# HMI.net
KiCad netlist of a schematic drawn in Altium Designer
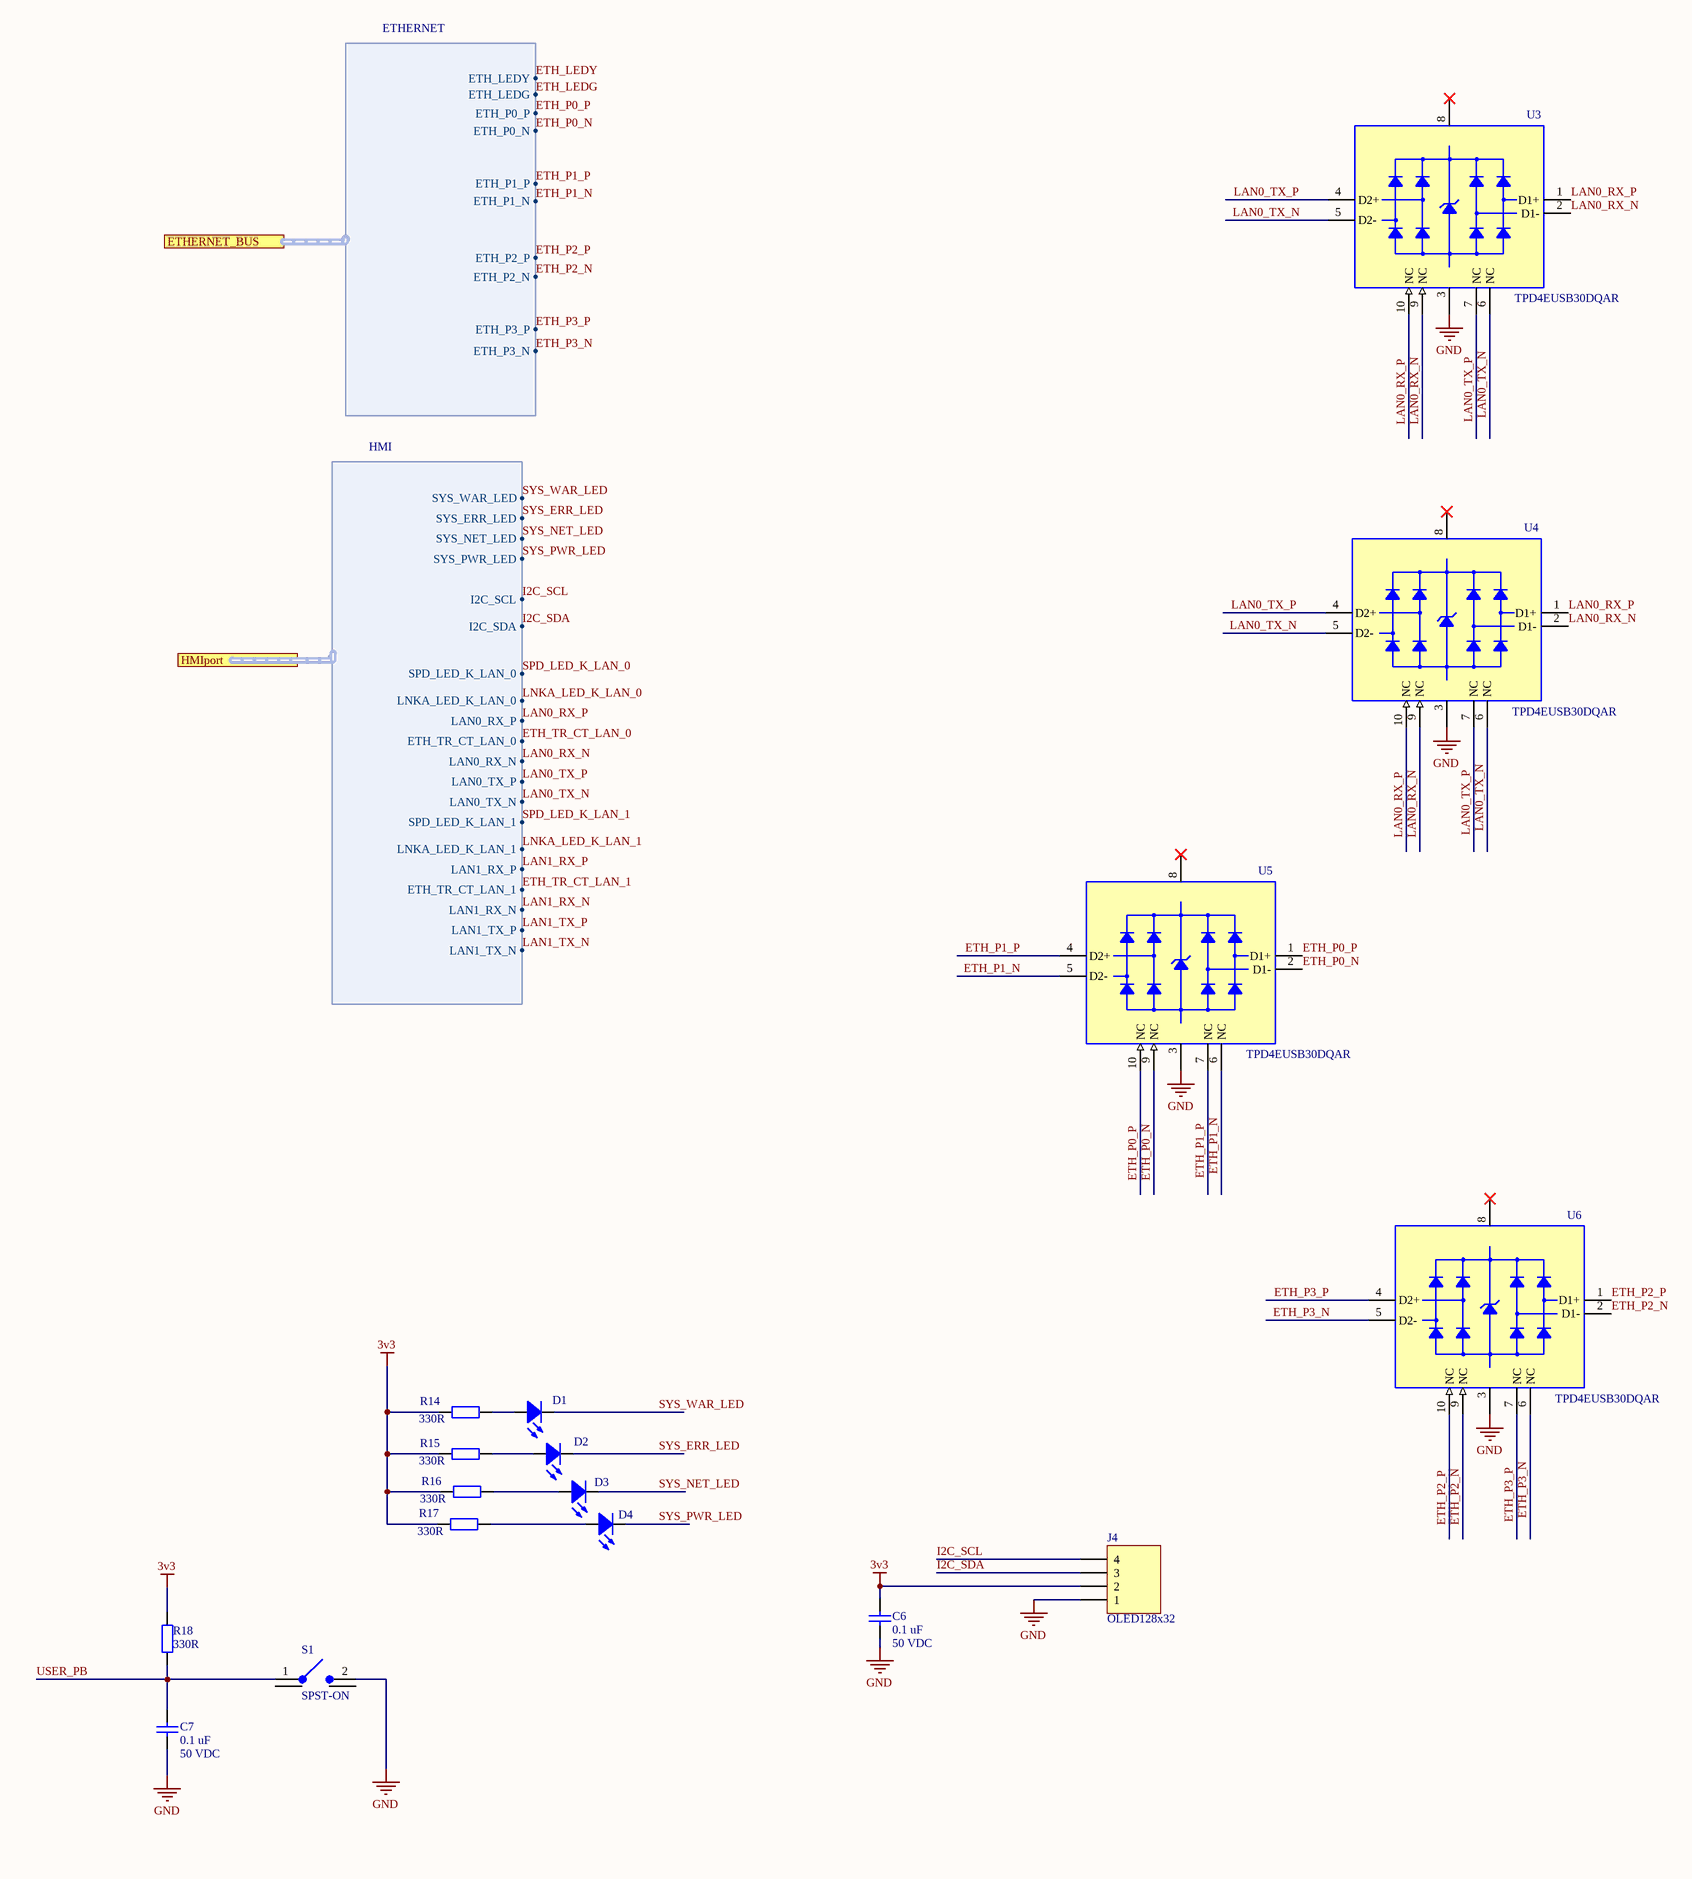
[diagram p0: HMI.SchDoc, left]
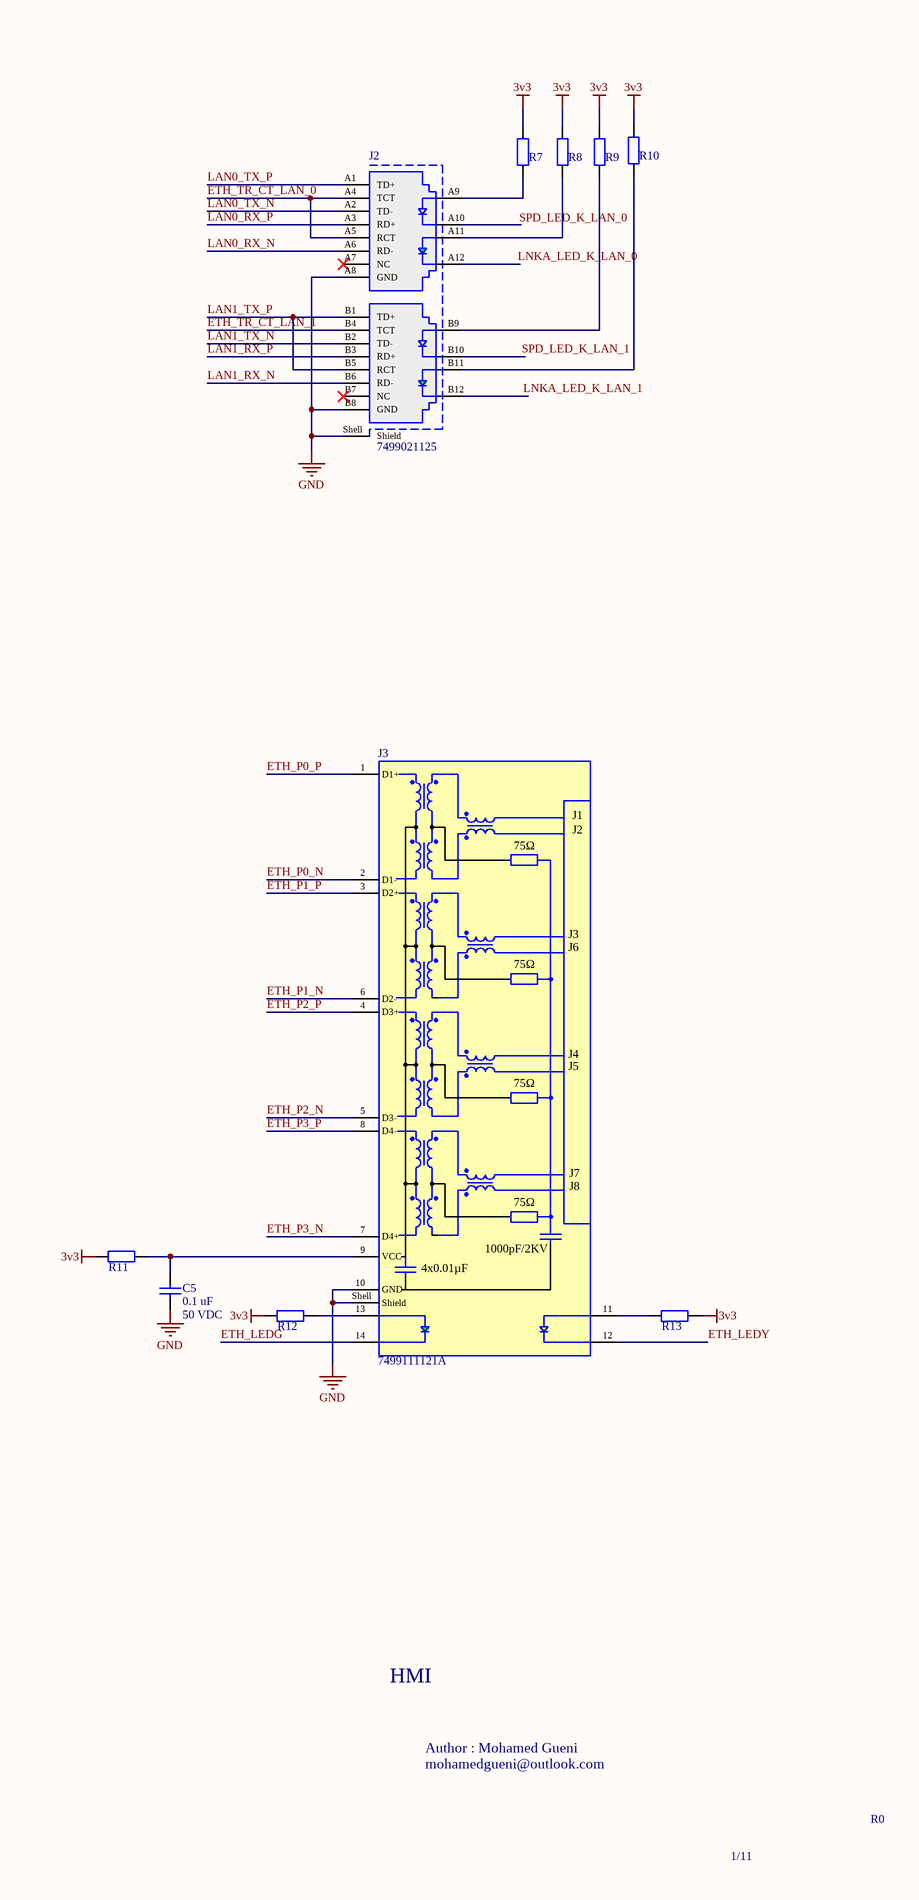
[diagram p1: HMI.SchDoc, right]

(export (version "E")
  (design (tool "Eeschema 10.0.6"))
  (components
    (comp (ref "C5")
      (value "Capacitor")
      (footprint "CAPC1608N")
      (fields
        (field (name "PART NUMBER") "CAP-000000003")
        (field (name "VALUE 1") "0.1 uF")
        (field (name "VALUE 2") "50 VDC")
      )
      (libsource (lib "DB") (part "Capacitor"))
    )
    (comp (ref "C6")
      (value "Capacitor")
      (footprint "CAPC1608N")
      (fields
        (field (name "PART NUMBER") "CAP-000000003")
        (field (name "VALUE 1") "0.1 uF")
        (field (name "VALUE 2") "50 VDC")
      )
      (libsource (lib "DB") (part "Capacitor"))
    )
    (comp (ref "C7")
      (value "Capacitor")
      (footprint "CAPC1608N")
      (fields
        (field (name "PART NUMBER") "CAP-000000003")
        (field (name "VALUE 1") "0.1 uF")
        (field (name "VALUE 2") "50 VDC")
      )
      (libsource (lib "DB") (part "Capacitor"))
    )
    (comp (ref "D1")
      (value "150060BS75000")
      (footprint "LED0603")
      (fields (field (name "PART NUMBER") "LED-000000003"))
      (libsource (lib "DB") (part "LED"))
    )
    (comp (ref "D2")
      (value "150060RS75000")
      (footprint "LED0603")
      (fields (field (name "PART NUMBER") "LED-000000001"))
      (libsource (lib "DB") (part "LED"))
    )
    (comp (ref "D3")
      (value "150060GS75000")
      (footprint "LED0603")
      (fields (field (name "PART NUMBER") "LED-000000002"))
      (libsource (lib "DB") (part "LED"))
    )
    (comp (ref "D4")
      (value "150060GS75000")
      (footprint "LED0603")
      (fields (field (name "PART NUMBER") "LED-000000002"))
      (libsource (lib "DB") (part "LED"))
    )
    (comp (ref "J2")
      (value "7499021125")
      (footprint "WE-RJ45-7499021125")
      (fields (field (name "PART NUMBER") "CON-000000008"))
      (libsource (lib "DB") (part "WE-RJ45-7499021125"))
    )
    (comp (ref "J3")
      (value "7499111121A")
      (footprint "WE-RJ45-7499111121A")
      (fields (field (name "PART NUMBER") "CON-000000002"))
      (libsource (lib "DB") (part "WE-RJ45-7499111121A"))
    )
    (comp (ref "J4")
      (value "OLED128x32")
      (footprint "OLED128x32")
      (fields (field (name "PART NUMBER") "CON-000000009"))
      (libsource (lib "DB") (part "OLED128x32"))
    )
    (comp (ref "R7")
      (value "Resistor")
      (footprint "RESC1608N")
      (fields (field (name "PART NUMBER") "RES-000000008"))
      (libsource (lib "") (part "Resistor_1"))
    )
    (comp (ref "R8")
      (value "Resistor")
      (footprint "RESC1608N")
      (fields (field (name "PART NUMBER") "RES-000000008"))
      (libsource (lib "") (part "Resistor_1"))
    )
    (comp (ref "R9")
      (value "Resistor")
      (footprint "RESC1608N")
      (fields (field (name "PART NUMBER") "RES-000000008"))
      (libsource (lib "") (part "Resistor_1"))
    )
    (comp (ref "R10")
      (value "Resistor")
      (footprint "RESC1608N")
      (fields (field (name "PART NUMBER") "RES-000000008"))
      (libsource (lib "") (part "Resistor_1"))
    )
    (comp (ref "R11")
      (value "Resistor")
      (footprint "RESC1608N")
      (fields (field (name "PART NUMBER") "RES-000000008"))
      (libsource (lib "") (part "Resistor_2"))
    )
    (comp (ref "R12")
      (value "Resistor")
      (footprint "RESC1608N")
      (fields (field (name "PART NUMBER") "RES-000000008"))
      (libsource (lib "") (part "Resistor_2"))
    )
    (comp (ref "R13")
      (value "Resistor")
      (footprint "RESC1608N")
      (fields (field (name "PART NUMBER") "RES-000000008"))
      (libsource (lib "DB") (part "Resistor"))
    )
    (comp (ref "R14")
      (value "Resistor")
      (footprint "RESC1608N")
      (fields (field (name "PART NUMBER") "RES-000000008") (field (name "VALUE 1") "330R"))
      (libsource (lib "DB") (part "Resistor"))
    )
    (comp (ref "R15")
      (value "Resistor")
      (footprint "RESC1608N")
      (fields (field (name "PART NUMBER") "RES-000000008") (field (name "VALUE 1") "330R"))
      (libsource (lib "DB") (part "Resistor"))
    )
    (comp (ref "R16")
      (value "Resistor")
      (footprint "RESC1608N")
      (fields (field (name "PART NUMBER") "RES-000000008") (field (name "VALUE 1") "330R"))
      (libsource (lib "DB") (part "Resistor"))
    )
    (comp (ref "R17")
      (value "Resistor")
      (footprint "RESC1608N")
      (fields (field (name "PART NUMBER") "RES-000000008") (field (name "VALUE 1") "330R"))
      (libsource (lib "DB") (part "Resistor"))
    )
    (comp (ref "R18")
      (value "Resistor")
      (footprint "RESC1608N")
      (fields (field (name "PART NUMBER") "RES-000000008") (field (name "VALUE 1") "330R"))
      (libsource (lib "") (part "Resistor_1"))
    )
    (comp (ref "S1")
      (value "SPST-ON")
      (footprint "118250272")
      (fields (field (name "PART NUMBER") "S-000000001"))
      (libsource (lib "DB") (part "SPST-ON"))
    )
    (comp (ref "U3")
      (value "TPD4EUSB30DQAR")
      (footprint "USON-10")
      (fields (field (name "PART NUMBER") "TVS-000000001"))
      (libsource (lib "DB") (part "TVS4"))
    )
    (comp (ref "U4")
      (value "TPD4EUSB30DQAR")
      (footprint "USON-10")
      (fields (field (name "PART NUMBER") "TVS-000000001"))
      (libsource (lib "DB") (part "TVS4"))
    )
    (comp (ref "U5")
      (value "TPD4EUSB30DQAR")
      (footprint "USON-10")
      (fields (field (name "PART NUMBER") "TVS-000000001"))
      (libsource (lib "DB") (part "TVS4"))
    )
    (comp (ref "U6")
      (value "TPD4EUSB30DQAR")
      (footprint "USON-10")
      (fields (field (name "PART NUMBER") "TVS-000000001"))
      (libsource (lib "DB") (part "TVS4"))
    )
  )
  (nets
    (net (code "3") (name "/ETH_LEDG") (class "Default")
      (node (ref "J3") (pin "14") (pinfunction "14_14") (pintype "passive"))
    )
    (net (code "4") (name "/ETH_LEDY") (class "Default")
      (node (ref "J3") (pin "12") (pinfunction "12_12") (pintype "passive"))
    )
    (net (code "5") (name "/ETH_P0_N") (class "Default")
      (node (ref "J3") (pin "2") (pinfunction "D1-_2") (pintype "passive"))
      (node (ref "U5") (pin "2") (pinfunction "D1-_2") (pintype "passive"))
      (node (ref "U5") (pin "9") (pinfunction "NC_9") (pintype "input"))
    )
    (net (code "6") (name "/ETH_P0_P") (class "Default")
      (node (ref "J3") (pin "1") (pinfunction "D1+_1") (pintype "passive"))
      (node (ref "U5") (pin "1") (pinfunction "D1+_1") (pintype "passive"))
      (node (ref "U5") (pin "10") (pinfunction "NC_10") (pintype "input"))
    )
    (net (code "7") (name "/ETH_P1_N") (class "Default")
      (node (ref "J3") (pin "6") (pinfunction "D2-_6") (pintype "passive"))
      (node (ref "U5") (pin "5") (pinfunction "D2-_5") (pintype "passive"))
      (node (ref "U5") (pin "6") (pinfunction "NC_6") (pintype "passive"))
    )
    (net (code "8") (name "/ETH_P1_P") (class "Default")
      (node (ref "J3") (pin "3") (pinfunction "D2+_3") (pintype "passive"))
      (node (ref "U5") (pin "4") (pinfunction "D2+_4") (pintype "passive"))
      (node (ref "U5") (pin "7") (pinfunction "NC_7") (pintype "passive"))
    )
    (net (code "9") (name "/ETH_P2_N") (class "Default")
      (node (ref "J3") (pin "5") (pinfunction "D3-_5") (pintype "passive"))
      (node (ref "U6") (pin "2") (pinfunction "D1-_2") (pintype "passive"))
      (node (ref "U6") (pin "9") (pinfunction "NC_9") (pintype "input"))
    )
    (net (code "10") (name "/ETH_P2_P") (class "Default")
      (node (ref "J3") (pin "4") (pinfunction "D3+_4") (pintype "passive"))
      (node (ref "U6") (pin "1") (pinfunction "D1+_1") (pintype "passive"))
      (node (ref "U6") (pin "10") (pinfunction "NC_10") (pintype "input"))
    )
    (net (code "11") (name "/ETH_P3_N") (class "Default")
      (node (ref "J3") (pin "7") (pinfunction "D4+_7") (pintype "passive"))
      (node (ref "U6") (pin "5") (pinfunction "D2-_5") (pintype "passive"))
      (node (ref "U6") (pin "6") (pinfunction "NC_6") (pintype "passive"))
    )
    (net (code "12") (name "/ETH_P3_P") (class "Default")
      (node (ref "J3") (pin "8") (pinfunction "D4-_8") (pintype "passive"))
      (node (ref "U6") (pin "4") (pinfunction "D2+_4") (pintype "passive"))
      (node (ref "U6") (pin "7") (pinfunction "NC_7") (pintype "passive"))
    )
    (net (code "13") (name "/ETH_TR_CT_LAN_0") (class "Default")
      (node (ref "J2") (pin "A4") (pinfunction "TCT_A4") (pintype "passive"))
      (node (ref "J2") (pin "A5") (pinfunction "RCT_A5") (pintype "passive"))
    )
    (net (code "14") (name "/ETH_TR_CT_LAN_1") (class "Default")
      (node (ref "J2") (pin "B4") (pinfunction "TCT_B4") (pintype "passive"))
    )
    (net (code "15") (name "/I2C_SCL") (class "Default")
      (node (ref "J4") (pin "4") (pinfunction "4_4") (pintype "passive"))
    )
    (net (code "16") (name "/I2C_SDA") (class "Default")
      (node (ref "J4") (pin "3") (pinfunction "3_3") (pintype "passive"))
    )
    (net (code "17") (name "/LAN0_RX_N") (class "Default")
      (node (ref "J2") (pin "A6") (pinfunction "RD-_A6") (pintype "passive"))
      (node (ref "U3") (pin "2") (pinfunction "D1-_2") (pintype "passive"))
      (node (ref "U3") (pin "9") (pinfunction "NC_9") (pintype "input"))
      (node (ref "U4") (pin "2") (pinfunction "D1-_2") (pintype "passive"))
      (node (ref "U4") (pin "9") (pinfunction "NC_9") (pintype "input"))
    )
    (net (code "18") (name "/LAN0_RX_P") (class "Default")
      (node (ref "J2") (pin "A3") (pinfunction "RD+_A3") (pintype "passive"))
      (node (ref "U3") (pin "1") (pinfunction "D1+_1") (pintype "passive"))
      (node (ref "U3") (pin "10") (pinfunction "NC_10") (pintype "input"))
      (node (ref "U4") (pin "1") (pinfunction "D1+_1") (pintype "passive"))
      (node (ref "U4") (pin "10") (pinfunction "NC_10") (pintype "input"))
    )
    (net (code "19") (name "/LAN0_TX_N") (class "Default")
      (node (ref "J2") (pin "A2") (pinfunction "TD-_A2") (pintype "passive"))
      (node (ref "U3") (pin "5") (pinfunction "D2-_5") (pintype "passive"))
      (node (ref "U3") (pin "6") (pinfunction "NC_6") (pintype "passive"))
      (node (ref "U4") (pin "5") (pinfunction "D2-_5") (pintype "passive"))
      (node (ref "U4") (pin "6") (pinfunction "NC_6") (pintype "passive"))
    )
    (net (code "20") (name "/LAN0_TX_P") (class "Default")
      (node (ref "J2") (pin "A1") (pinfunction "TD+_A1") (pintype "passive"))
      (node (ref "U3") (pin "4") (pinfunction "D2+_4") (pintype "passive"))
      (node (ref "U3") (pin "7") (pinfunction "NC_7") (pintype "passive"))
      (node (ref "U4") (pin "4") (pinfunction "D2+_4") (pintype "passive"))
      (node (ref "U4") (pin "7") (pinfunction "NC_7") (pintype "passive"))
    )
    (net (code "21") (name "/LAN1_RX_N") (class "Default")
      (node (ref "J2") (pin "B6") (pinfunction "RD-_B6") (pintype "passive"))
    )
    (net (code "22") (name "/LAN1_RX_P") (class "Default")
      (node (ref "J2") (pin "B3") (pinfunction "RD+_B3") (pintype "passive"))
    )
    (net (code "23") (name "/LAN1_TX_N") (class "Default")
      (node (ref "J2") (pin "B2") (pinfunction "TD-_B2") (pintype "passive"))
    )
    (net (code "24") (name "/LAN1_TX_P") (class "Default")
      (node (ref "J2") (pin "B1") (pinfunction "TD+_B1") (pintype "passive"))
      (node (ref "J2") (pin "B5") (pinfunction "RCT_B5") (pintype "passive"))
    )
    (net (code "25") (name "/LNKA_LED_K_LAN_0") (class "Default")
      (node (ref "J2") (pin "A12") (pinfunction "A12_A12") (pintype "passive"))
    )
    (net (code "26") (name "/LNKA_LED_K_LAN_1") (class "Default")
      (node (ref "J2") (pin "B12") (pinfunction "B12_B12") (pintype "passive"))
    )
    (net (code "28") (name "/SPD_LED_K_LAN_1") (class "Default")
      (node (ref "J2") (pin "B10") (pinfunction "B10_B10") (pintype "passive"))
    )
    (net (code "29") (name "/SYS_ERR_LED") (class "Default")
      (node (ref "D2") (pin "1") (pinfunction "K_1") (pintype "passive"))
    )
    (net (code "30") (name "/SYS_NET_LED") (class "Default")
      (node (ref "D3") (pin "1") (pinfunction "K_1") (pintype "passive"))
    )
    (net (code "31") (name "/SYS_PWR_LED") (class "Default")
      (node (ref "D4") (pin "1") (pinfunction "K_1") (pintype "passive"))
    )
    (net (code "32") (name "/SYS_WAR_LED") (class "Default")
      (node (ref "D1") (pin "1") (pinfunction "K_1") (pintype "passive"))
    )
    (net (code "33") (name "/USER_PB") (class "Default")
      (node (ref "C7") (pin "2") (pinfunction "2_2") (pintype "passive"))
      (node (ref "R18") (pin "1") (pinfunction "1_1") (pintype "passive"))
      (node (ref "S1") (pin "1") (pinfunction "COM_1") (pintype "passive"))
    )
    (net (code "36") (name "3v3") (class "Default")
      (node (ref "C6") (pin "2") (pinfunction "2_2") (pintype "passive"))
      (node (ref "J4") (pin "2") (pinfunction "2_2") (pintype "passive"))
      (node (ref "R10") (pin "2") (pinfunction "2_2") (pintype "passive"))
      (node (ref "R11") (pin "2") (pinfunction "2_2") (pintype "passive"))
      (node (ref "R12") (pin "2") (pinfunction "2_2") (pintype "passive"))
      (node (ref "R13") (pin "2") (pinfunction "2_2") (pintype "passive"))
      (node (ref "R14") (pin "1") (pinfunction "1_1") (pintype "passive"))
      (node (ref "R15") (pin "1") (pinfunction "1_1") (pintype "passive"))
      (node (ref "R16") (pin "1") (pinfunction "1_1") (pintype "passive"))
      (node (ref "R17") (pin "1") (pinfunction "1_1") (pintype "passive"))
      (node (ref "R18") (pin "2") (pinfunction "2_2") (pintype "passive"))
      (node (ref "R7") (pin "2") (pinfunction "2_2") (pintype "passive"))
      (node (ref "R8") (pin "2") (pinfunction "2_2") (pintype "passive"))
      (node (ref "R9") (pin "2") (pinfunction "2_2") (pintype "passive"))
    )
    (net (code "37") (name "GND") (class "Default")
      (node (ref "C5") (pin "1") (pinfunction "1_1") (pintype "passive"))
      (node (ref "C6") (pin "1") (pinfunction "1_1") (pintype "passive"))
      (node (ref "C7") (pin "1") (pinfunction "1_1") (pintype "passive"))
      (node (ref "J2") (pin "A8") (pinfunction "GND_A8") (pintype "passive"))
      (node (ref "J2") (pin "B8") (pinfunction "GND_B8") (pintype "passive"))
      (node (ref "J2") (pin "Shell") (pinfunction "Shield_Shell") (pintype "passive"))
      (node (ref "J3") (pin "10") (pinfunction "GND_10") (pintype "passive"))
      (node (ref "J3") (pin "Shell") (pinfunction "Shield_Shell") (pintype "passive"))
      (node (ref "J4") (pin "1") (pinfunction "1_1") (pintype "passive"))
      (node (ref "S1") (pin "2") (pinfunction "NO_2") (pintype "passive"))
      (node (ref "U3") (pin "3") (pinfunction "GND_3") (pintype "passive"))
      (node (ref "U4") (pin "3") (pinfunction "GND_3") (pintype "passive"))
      (node (ref "U5") (pin "3") (pinfunction "GND_3") (pintype "passive"))
      (node (ref "U6") (pin "3") (pinfunction "GND_3") (pintype "passive"))
    )
    (net (code "38") (name "Net-(D1-A)") (class "Default")
      (node (ref "D1") (pin "2") (pinfunction "A_2") (pintype "passive"))
      (node (ref "R14") (pin "2") (pinfunction "2_2") (pintype "passive"))
    )
    (net (code "39") (name "Net-(D2-A)") (class "Default")
      (node (ref "D2") (pin "2") (pinfunction "A_2") (pintype "passive"))
      (node (ref "R15") (pin "2") (pinfunction "2_2") (pintype "passive"))
    )
    (net (code "40") (name "Net-(D3-A)") (class "Default")
      (node (ref "D3") (pin "2") (pinfunction "A_2") (pintype "passive"))
      (node (ref "R16") (pin "2") (pinfunction "2_2") (pintype "passive"))
    )
    (net (code "41") (name "Net-(D4-A)") (class "Default")
      (node (ref "D4") (pin "2") (pinfunction "A_2") (pintype "passive"))
      (node (ref "R17") (pin "2") (pinfunction "2_2") (pintype "passive"))
    )
    (net (code "42") (name "Net-(J2-PadA9)") (class "Default")
      (node (ref "J2") (pin "A9") (pinfunction "A9_A9") (pintype "passive"))
      (node (ref "R7") (pin "1") (pinfunction "1_1") (pintype "passive"))
    )
    (net (code "43") (name "Net-(J2-PadA11)") (class "Default")
      (node (ref "J2") (pin "A11") (pinfunction "A11_A11") (pintype "passive"))
      (node (ref "R8") (pin "1") (pinfunction "1_1") (pintype "passive"))
    )
    (net (code "44") (name "Net-(J2-PadB9)") (class "Default")
      (node (ref "J2") (pin "B9") (pinfunction "B9_B9") (pintype "passive"))
      (node (ref "R9") (pin "1") (pinfunction "1_1") (pintype "passive"))
    )
    (net (code "45") (name "Net-(J2-PadB11)") (class "Default")
      (node (ref "J2") (pin "B11") (pinfunction "B11_B11") (pintype "passive"))
      (node (ref "R10") (pin "1") (pinfunction "1_1") (pintype "passive"))
    )
    (net (code "46") (name "Net-(J3-Pad11)") (class "Default")
      (node (ref "J3") (pin "11") (pinfunction "11_11") (pintype "passive"))
      (node (ref "R13") (pin "1") (pinfunction "1_1") (pintype "passive"))
    )
    (net (code "47") (name "Net-(J3-Pad13)") (class "Default")
      (node (ref "J3") (pin "13") (pinfunction "13_13") (pintype "passive"))
      (node (ref "R12") (pin "1") (pinfunction "1_1") (pintype "passive"))
    )
    (net (code "48") (name "Net-(J3-VCC)") (class "Default")
      (node (ref "C5") (pin "2") (pinfunction "2_2") (pintype "passive"))
      (node (ref "J3") (pin "9") (pinfunction "VCC_9") (pintype "passive"))
      (node (ref "R11") (pin "1") (pinfunction "1_1") (pintype "passive"))
    )
    (net (code "49") (name "unconnected-(J2-NC-PadA7)") (class "Default")
      (node (ref "J2") (pin "A7") (pinfunction "NC_A7") (pintype "passive+no_connect"))
    )
    (net (code "50") (name "unconnected-(J2-NC-PadB7)") (class "Default")
      (node (ref "J2") (pin "B7") (pinfunction "NC_B7") (pintype "passive+no_connect"))
    )
    (net (code "51") (name "unconnected-(J2-PadA10)") (class "Default")
      (node (ref "J2") (pin "A10") (pinfunction "A10_A10") (pintype "passive"))
    )
    (net (code "52") (name "unconnected-(S1-PadMH1)") (class "Default")
      (node (ref "S1") (pin "MH1") (pinfunction "MH1_MH1") (pintype "passive"))
    )
    (net (code "53") (name "unconnected-(S1-PadMH2)") (class "Default")
      (node (ref "S1") (pin "MH2") (pinfunction "MH2_MH2") (pintype "passive"))
    )
    (net (code "54") (name "unconnected-(U3-GND-Pad8)") (class "Default")
      (node (ref "U3") (pin "8") (pinfunction "GND_8") (pintype "passive+no_connect"))
    )
    (net (code "55") (name "unconnected-(U4-GND-Pad8)") (class "Default")
      (node (ref "U4") (pin "8") (pinfunction "GND_8") (pintype "passive+no_connect"))
    )
    (net (code "56") (name "unconnected-(U5-GND-Pad8)") (class "Default")
      (node (ref "U5") (pin "8") (pinfunction "GND_8") (pintype "passive+no_connect"))
    )
    (net (code "57") (name "unconnected-(U6-GND-Pad8)") (class "Default")
      (node (ref "U6") (pin "8") (pinfunction "GND_8") (pintype "passive+no_connect"))
    )
  )
)
